# 08-_-.net
KiCad netlist of a schematic drawn in Altium Designer
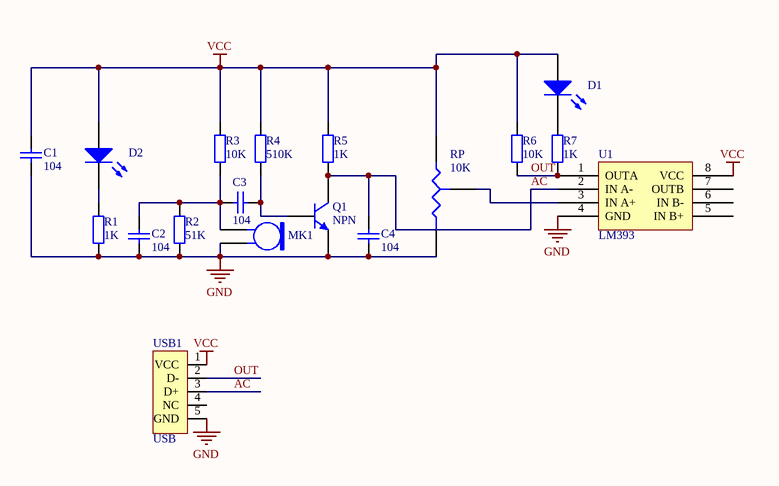
[diagram p0: 08-声音传感器模块-原理图.SchDoc]

(export (version "E")
  (design (tool "Eeschema 10.0.6"))
  (components
    (comp (ref "C1")
      (value "104")
      (footprint "0805")
      (description "Capacitor")
      (fields (field (name "Comment") "Cap") (field (name "PUBLISHER") "Altium Limited"))
      (libsource (lib "Miscellaneous Devices") (part "Cap"))
    )
    (comp (ref "C2")
      (value "104")
      (footprint "0805")
      (description "Capacitor")
      (fields (field (name "Comment") "Cap") (field (name "PUBLISHER") "Altium Limited"))
      (libsource (lib "Miscellaneous Devices") (part "Cap"))
    )
    (comp (ref "C3")
      (value "104")
      (footprint "0805")
      (description "Capacitor")
      (fields (field (name "Comment") "Cap") (field (name "PUBLISHER") "Altium Limited"))
      (libsource (lib "Miscellaneous Devices") (part "Cap"))
    )
    (comp (ref "C4")
      (value "104")
      (footprint "0805")
      (description "Capacitor")
      (fields (field (name "Comment") "Cap") (field (name "PUBLISHER") "Altium Limited"))
      (libsource (lib "Miscellaneous Devices") (part "Cap"))
    )
    (comp (ref "D1")
      (value "LED0")
      (footprint "0805")
      (description "Typical INFRARED GaAs LED")
      (fields (field (name "PUBLISHER") "Altium Limited"))
      (libsource (lib "Miscellaneous Devices") (part "LED0"))
    )
    (comp (ref "D2")
      (value "LED0")
      (footprint "0805")
      (description "Typical INFRARED GaAs LED")
      (fields (field (name "PUBLISHER") "Altium Limited"))
      (libsource (lib "Miscellaneous Devices") (part "LED0"))
    )
    (comp (ref "MK1")
      (value "Mic2")
      (footprint "MT")
      (description "Microphone")
      (fields (field (name "PUBLISHER") "Altium Limited"))
      (libsource (lib "Miscellaneous Devices") (part "Mic2"))
    )
    (comp (ref "Q1")
      (value "NPN")
      (footprint "sot-23")
      (description "NPN Bipolar Transistor")
      (fields (field (name "PUBLISHER") "Altium Limited"))
      (libsource (lib "Miscellaneous Devices") (part "QNPN"))
    )
    (comp (ref "R1")
      (value "1K")
      (footprint "0805")
      (description "Resistor")
      (fields (field (name "Comment") "res2") (field (name "PUBLISHER") "Altium Limited"))
      (libsource (lib "Miscellaneous Devices") (part "Res2"))
    )
    (comp (ref "R2")
      (value "51K")
      (footprint "0805")
      (description "Resistor")
      (fields (field (name "Comment") "res2") (field (name "PUBLISHER") "Altium Limited"))
      (libsource (lib "Miscellaneous Devices") (part "Res2"))
    )
    (comp (ref "R3")
      (value "10K")
      (footprint "0805")
      (description "Resistor")
      (fields (field (name "Comment") "res2") (field (name "PUBLISHER") "Altium Limited"))
      (libsource (lib "Miscellaneous Devices") (part "Res2"))
    )
    (comp (ref "R4")
      (value "510K")
      (footprint "0805")
      (description "Resistor")
      (fields (field (name "Comment") "res2") (field (name "PUBLISHER") "Altium Limited"))
      (libsource (lib "Miscellaneous Devices") (part "Res2"))
    )
    (comp (ref "R5")
      (value "1K")
      (footprint "0805")
      (description "Resistor")
      (fields (field (name "Comment") "res2") (field (name "PUBLISHER") "Altium Limited"))
      (libsource (lib "Miscellaneous Devices") (part "Res2"))
    )
    (comp (ref "R6")
      (value "10K")
      (footprint "0805")
      (description "Resistor")
      (fields (field (name "Comment") "res2") (field (name "PUBLISHER") "Altium Limited"))
      (libsource (lib "Miscellaneous Devices") (part "Res2"))
    )
    (comp (ref "R7")
      (value "1K")
      (footprint "0805")
      (description "Resistor")
      (fields (field (name "Comment") "res2") (field (name "PUBLISHER") "Altium Limited"))
      (libsource (lib "Miscellaneous Devices") (part "Res2"))
    )
    (comp (ref "RP")
      (value "10K")
      (footprint "VR")
      (description "Tapped Resistor")
      (fields (field (name "Comment") "Res Tap") (field (name "PUBLISHER") "Altium Limited"))
      (libsource (lib "Miscellaneous Devices") (part "Res Tap"))
    )
    (comp (ref "U1") (value "LM393") (footprint "SOP-8") (libsource (lib "原理图库") (part "LM393")))
    (comp (ref "USB1") (value "USB") (footprint "USB/SM0.8-6H5") (libsource (lib "原理图库") (part "USB5")))
  )
  (nets
    (net (code "1") (name "/AC") (class "Default")
      (node (ref "C4") (pin "1") (pinfunction "1_1") (pintype "passive"))
      (node (ref "Q1") (pin "3") (pinfunction "C_3") (pintype "passive"))
      (node (ref "R5") (pin "1") (pinfunction "1_1") (pintype "passive"))
      (node (ref "U1") (pin "2") (pinfunction "IN_A-_2") (pintype "passive"))
      (node (ref "USB1") (pin "3") (pinfunction "D+_3") (pintype "passive"))
    )
    (net (code "2") (name "/OUT") (class "Default")
      (node (ref "R6") (pin "1") (pinfunction "1_1") (pintype "passive"))
      (node (ref "R7") (pin "1") (pinfunction "1_1") (pintype "passive"))
      (node (ref "U1") (pin "1") (pinfunction "OUTA_1") (pintype "passive"))
      (node (ref "USB1") (pin "2") (pinfunction "D-_2") (pintype "passive"))
    )
    (net (code "3") (name "GND") (class "Default")
      (node (ref "C1") (pin "1") (pinfunction "1_1") (pintype "passive"))
      (node (ref "C2") (pin "1") (pinfunction "1_1") (pintype "passive"))
      (node (ref "C4") (pin "2") (pinfunction "2_2") (pintype "passive"))
      (node (ref "MK1") (pin "2") (pinfunction "2_2") (pintype "passive"))
      (node (ref "Q1") (pin "2") (pinfunction "E_2") (pintype "passive"))
      (node (ref "R1") (pin "1") (pinfunction "1_1") (pintype "passive"))
      (node (ref "R2") (pin "1") (pinfunction "1_1") (pintype "passive"))
      (node (ref "RP") (pin "2") (pinfunction "B_2") (pintype "passive"))
      (node (ref "U1") (pin "4") (pinfunction "GND_4") (pintype "passive"))
      (node (ref "USB1") (pin "5") (pinfunction "GND_5") (pintype "passive"))
    )
    (net (code "4") (name "Net-(C2-Pad2)") (class "Default")
      (node (ref "C2") (pin "2") (pinfunction "2_2") (pintype "passive"))
      (node (ref "C3") (pin "2") (pinfunction "2_2") (pintype "passive"))
      (node (ref "MK1") (pin "1") (pinfunction "1_1") (pintype "passive"))
      (node (ref "R2") (pin "2") (pinfunction "2_2") (pintype "passive"))
      (node (ref "R3") (pin "1") (pinfunction "1_1") (pintype "passive"))
    )
    (net (code "5") (name "Net-(D1-K)") (class "Default")
      (node (ref "D1") (pin "2") (pinfunction "K_2") (pintype "passive"))
      (node (ref "R7") (pin "2") (pinfunction "2_2") (pintype "passive"))
    )
    (net (code "6") (name "Net-(D2-K)") (class "Default")
      (node (ref "D2") (pin "2") (pinfunction "K_2") (pintype "passive"))
      (node (ref "R1") (pin "2") (pinfunction "2_2") (pintype "passive"))
    )
    (net (code "7") (name "Net-(Q1-B)") (class "Default")
      (node (ref "C3") (pin "1") (pinfunction "1_1") (pintype "passive"))
      (node (ref "Q1") (pin "1") (pinfunction "B_1") (pintype "passive"))
      (node (ref "R4") (pin "1") (pinfunction "1_1") (pintype "passive"))
    )
    (net (code "8") (name "Net-(RP-TAP)") (class "Default")
      (node (ref "RP") (pin "3") (pinfunction "TAP_3") (pintype "passive"))
      (node (ref "U1") (pin "3") (pinfunction "IN_A+_3") (pintype "passive"))
    )
    (net (code "9") (name "VCC") (class "Default")
      (node (ref "C1") (pin "2") (pinfunction "2_2") (pintype "passive"))
      (node (ref "D1") (pin "1") (pinfunction "A_1") (pintype "passive"))
      (node (ref "D2") (pin "1") (pinfunction "A_1") (pintype "passive"))
      (node (ref "R3") (pin "2") (pinfunction "2_2") (pintype "passive"))
      (node (ref "R4") (pin "2") (pinfunction "2_2") (pintype "passive"))
      (node (ref "R5") (pin "2") (pinfunction "2_2") (pintype "passive"))
      (node (ref "R6") (pin "2") (pinfunction "2_2") (pintype "passive"))
      (node (ref "RP") (pin "1") (pinfunction "A_1") (pintype "passive"))
      (node (ref "U1") (pin "8") (pinfunction "VCC_8") (pintype "passive"))
      (node (ref "USB1") (pin "1") (pinfunction "VCC_1") (pintype "passive"))
    )
    (net (code "10") (name "unconnected-(U1-IN_B+-Pad5)") (class "Default")
      (node (ref "U1") (pin "5") (pinfunction "IN_B+_5") (pintype "passive"))
    )
    (net (code "11") (name "unconnected-(U1-IN_B--Pad6)") (class "Default")
      (node (ref "U1") (pin "6") (pinfunction "IN_B-_6") (pintype "passive"))
    )
    (net (code "12") (name "unconnected-(U1-OUTB-Pad7)") (class "Default")
      (node (ref "U1") (pin "7") (pinfunction "OUTB_7") (pintype "passive"))
    )
    (net (code "13") (name "unconnected-(USB1-NC-Pad4)") (class "Default")
      (node (ref "USB1") (pin "4") (pinfunction "NC_4") (pintype "passive"))
    )
  )
)
